# IO.net
KiCad netlist of a schematic drawn in Altium Designer
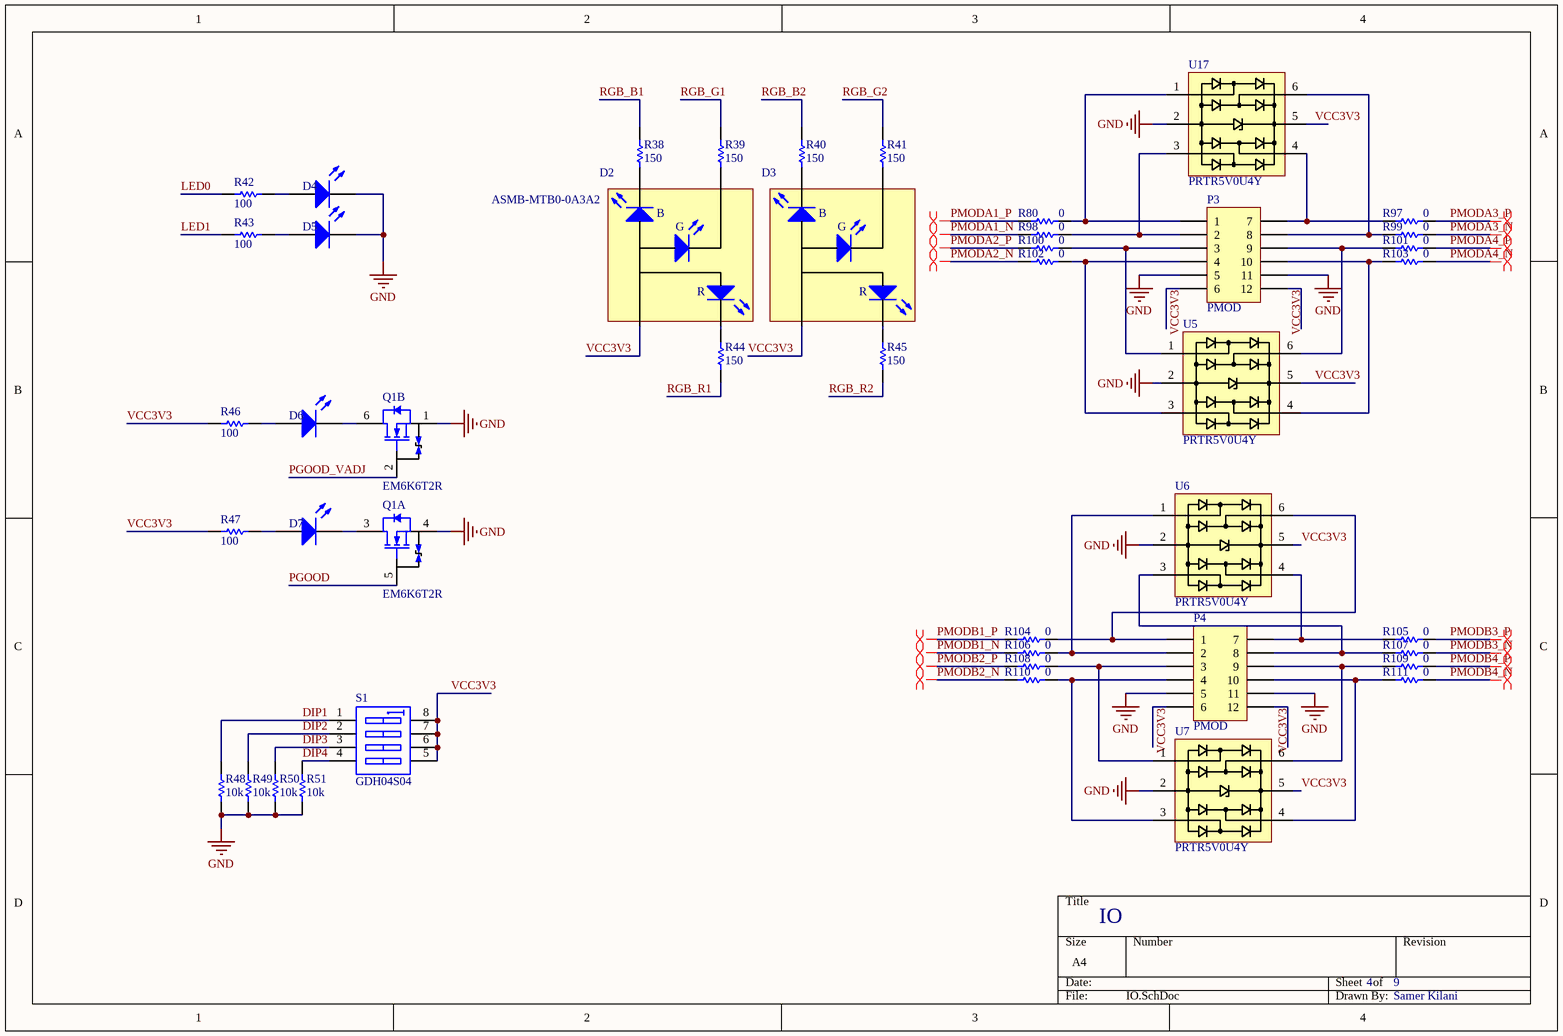
[diagram p0: IO.SchDoc]

(export (version "E")
  (design (tool "Eeschema 10.0.6"))
  (components
    (comp (ref "D2")
      (value "ASMB-MTB0-0A3A2")
      (footprint "ASMB-MTB0-0A3A2")
      (description "Typical INFRARED GaAs LED")
      (fields (field (name "PUBLISHER") "Altium Limited"))
      (libsource (lib "atfclib") (part "LED_RGB"))
    )
    (comp (ref "D3")
      (value "ASMB-MTB0-0A3A2")
      (footprint "ASMB-MTB0-0A3A2")
      (description "Typical INFRARED GaAs LED")
      (fields (field (name "PUBLISHER") "Altium Limited"))
      (libsource (lib "atfclib") (part "LED_RGB"))
    )
    (comp (ref "D4")
      (value "KPT-1608EC")
      (footprint "KP-1608QBC-D")
      (fields (field (name "PUBLISHER") "Altium Limited"))
      (libsource (lib "atfclib") (part "LED"))
    )
    (comp (ref "D5")
      (value "KPT-1608EC")
      (footprint "KP-1608QBC-D")
      (fields (field (name "PUBLISHER") "Altium Limited"))
      (libsource (lib "atfclib") (part "LED"))
    )
    (comp (ref "D6")
      (value "KPT-1608EC")
      (footprint "KP-1608QBC-D")
      (fields (field (name "PUBLISHER") "Altium Limited"))
      (libsource (lib "atfclib") (part "LED"))
    )
    (comp (ref "D7")
      (value "KPT-1608EC")
      (footprint "KP-1608QBC-D")
      (fields (field (name "PUBLISHER") "Altium Limited"))
      (libsource (lib "atfclib") (part "LED"))
    )
    (comp (ref "P3")
      (value "PMOD")
      (footprint "PMOD_12")
      (description "Header, 6-Pin, Dual row")
      (fields (field (name "PUBLISHER") "Altium Limited"))
      (libsource (lib "Miscellaneous Connectors") (part "Header 6X2A"))
    )
    (comp (ref "P4")
      (value "PMOD")
      (footprint "PMOD_12")
      (description "Header, 6-Pin, Dual row")
      (fields (field (name "PUBLISHER") "Altium Limited"))
      (libsource (lib "Miscellaneous Connectors") (part "Header 6X2A"))
    )
    (comp (ref "Q1") (value "EM6K6T2R") (footprint "SOT-563") (libsource (lib "atfclib") (part "EM6K6")))
    (comp (ref "R38")
      (value "150")
      (footprint "R0402")
      (description "Resistor")
      (fields (field (name "Comment") "Res"))
      (libsource (lib "atfclib") (part "Res"))
    )
    (comp (ref "R39")
      (value "150")
      (footprint "R0402")
      (description "Resistor")
      (fields (field (name "Comment") "Res"))
      (libsource (lib "atfclib") (part "Res"))
    )
    (comp (ref "R40")
      (value "150")
      (footprint "R0402")
      (description "Resistor")
      (fields (field (name "Comment") "Res"))
      (libsource (lib "atfclib") (part "Res"))
    )
    (comp (ref "R41")
      (value "150")
      (footprint "R0402")
      (description "Resistor")
      (fields (field (name "Comment") "Res"))
      (libsource (lib "atfclib") (part "Res"))
    )
    (comp (ref "R42")
      (value "100")
      (footprint "R0402")
      (description "Resistor")
      (fields (field (name "Comment") "Res"))
      (libsource (lib "atfclib") (part "Res"))
    )
    (comp (ref "R43")
      (value "100")
      (footprint "R0402")
      (description "Resistor")
      (fields (field (name "Comment") "Res"))
      (libsource (lib "atfclib") (part "Res"))
    )
    (comp (ref "R44")
      (value "150")
      (footprint "R0402")
      (description "Resistor")
      (fields (field (name "Comment") "Res"))
      (libsource (lib "atfclib") (part "Res"))
    )
    (comp (ref "R45")
      (value "150")
      (footprint "R0402")
      (description "Resistor")
      (fields (field (name "Comment") "Res"))
      (libsource (lib "atfclib") (part "Res"))
    )
    (comp (ref "R46")
      (value "100")
      (footprint "R0402")
      (description "Resistor")
      (fields (field (name "Comment") "Res"))
      (libsource (lib "atfclib") (part "Res"))
    )
    (comp (ref "R47")
      (value "100")
      (footprint "R0402")
      (description "Resistor")
      (fields (field (name "Comment") "Res"))
      (libsource (lib "atfclib") (part "Res"))
    )
    (comp (ref "R48")
      (value "10k")
      (footprint "R0402")
      (description "Resistor")
      (fields (field (name "Comment") "Res"))
      (libsource (lib "atfclib") (part "Res"))
    )
    (comp (ref "R49")
      (value "10k")
      (footprint "R0402")
      (description "Resistor")
      (fields (field (name "Comment") "Res"))
      (libsource (lib "atfclib") (part "Res"))
    )
    (comp (ref "R50")
      (value "10k")
      (footprint "R0402")
      (description "Resistor")
      (fields (field (name "Comment") "Res"))
      (libsource (lib "atfclib") (part "Res"))
    )
    (comp (ref "R51")
      (value "10k")
      (footprint "R0402")
      (description "Resistor")
      (fields (field (name "Comment") "Res"))
      (libsource (lib "atfclib") (part "Res"))
    )
    (comp (ref "R80")
      (value "0")
      (footprint "R0402")
      (description "Resistor")
      (fields (field (name "Comment") "Res"))
      (libsource (lib "atfclib") (part "Res"))
    )
    (comp (ref "R97")
      (value "0")
      (footprint "R0402")
      (description "Resistor")
      (fields (field (name "Comment") "Res"))
      (libsource (lib "atfclib") (part "Res"))
    )
    (comp (ref "R98")
      (value "0")
      (footprint "R0402")
      (description "Resistor")
      (fields (field (name "Comment") "Res"))
      (libsource (lib "atfclib") (part "Res"))
    )
    (comp (ref "R99")
      (value "0")
      (footprint "R0402")
      (description "Resistor")
      (fields (field (name "Comment") "Res"))
      (libsource (lib "atfclib") (part "Res"))
    )
    (comp (ref "R100")
      (value "0")
      (footprint "R0402")
      (description "Resistor")
      (fields (field (name "Comment") "Res"))
      (libsource (lib "atfclib") (part "Res"))
    )
    (comp (ref "R101")
      (value "0")
      (footprint "R0402")
      (description "Resistor")
      (fields (field (name "Comment") "Res"))
      (libsource (lib "atfclib") (part "Res"))
    )
    (comp (ref "R102")
      (value "0")
      (footprint "R0402")
      (description "Resistor")
      (fields (field (name "Comment") "Res"))
      (libsource (lib "atfclib") (part "Res"))
    )
    (comp (ref "R103")
      (value "0")
      (footprint "R0402")
      (description "Resistor")
      (fields (field (name "Comment") "Res"))
      (libsource (lib "atfclib") (part "Res"))
    )
    (comp (ref "R104")
      (value "0")
      (footprint "R0402")
      (description "Resistor")
      (fields (field (name "Comment") "Res"))
      (libsource (lib "atfclib") (part "Res"))
    )
    (comp (ref "R105")
      (value "0")
      (footprint "R0402")
      (description "Resistor")
      (fields (field (name "Comment") "Res"))
      (libsource (lib "atfclib") (part "Res"))
    )
    (comp (ref "R106")
      (value "0")
      (footprint "R0402")
      (description "Resistor")
      (fields (field (name "Comment") "Res"))
      (libsource (lib "atfclib") (part "Res"))
    )
    (comp (ref "R107")
      (value "0")
      (footprint "R0402")
      (description "Resistor")
      (fields (field (name "Comment") "Res"))
      (libsource (lib "atfclib") (part "Res"))
    )
    (comp (ref "R108")
      (value "0")
      (footprint "R0402")
      (description "Resistor")
      (fields (field (name "Comment") "Res"))
      (libsource (lib "atfclib") (part "Res"))
    )
    (comp (ref "R109")
      (value "0")
      (footprint "R0402")
      (description "Resistor")
      (fields (field (name "Comment") "Res"))
      (libsource (lib "atfclib") (part "Res"))
    )
    (comp (ref "R110")
      (value "0")
      (footprint "R0402")
      (description "Resistor")
      (fields (field (name "Comment") "Res"))
      (libsource (lib "atfclib") (part "Res"))
    )
    (comp (ref "R111")
      (value "0")
      (footprint "R0402")
      (description "Resistor")
      (fields (field (name "Comment") "Res"))
      (libsource (lib "atfclib") (part "Res"))
    )
    (comp (ref "S1")
      (value "GDH04S04")
      (footprint "DIP-SOP8")
      (description "DIP Switch, 4 Position, SPST")
      (fields (field (name "PUBLISHER") "Altium Limited"))
      (libsource (lib "Miscellaneous Devices") (part "SW DIP-4"))
    )
    (comp (ref "U5")
      (value "PRTR5V0U4Y")
      (footprint "SOT363")
      (libsource (lib "atfclib") (part "PRTR5V0U4Y"))
    )
    (comp (ref "U6")
      (value "PRTR5V0U4Y")
      (footprint "SOT363")
      (libsource (lib "atfclib") (part "PRTR5V0U4Y"))
    )
    (comp (ref "U7")
      (value "PRTR5V0U4Y")
      (footprint "SOT363")
      (libsource (lib "atfclib") (part "PRTR5V0U4Y"))
    )
    (comp (ref "U17")
      (value "PRTR5V0U4Y")
      (footprint "SOT363")
      (libsource (lib "atfclib") (part "PRTR5V0U4Y"))
    )
  )
  (nets
    (net (code "1") (name "/DIP1") (class "Default")
      (node (ref "R48") (pin "1") (pinfunction "1_1") (pintype "passive"))
      (node (ref "S1") (pin "1") (pinfunction "A1_1") (pintype "passive"))
    )
    (net (code "2") (name "/DIP2") (class "Default")
      (node (ref "R49") (pin "1") (pinfunction "1_1") (pintype "passive"))
      (node (ref "S1") (pin "2") (pinfunction "A2_2") (pintype "passive"))
    )
    (net (code "3") (name "/DIP3") (class "Default")
      (node (ref "R50") (pin "1") (pinfunction "1_1") (pintype "passive"))
      (node (ref "S1") (pin "3") (pinfunction "A3_3") (pintype "passive"))
    )
    (net (code "4") (name "/DIP4") (class "Default")
      (node (ref "R51") (pin "1") (pinfunction "1_1") (pintype "passive"))
      (node (ref "S1") (pin "4") (pinfunction "A4_4") (pintype "passive"))
    )
    (net (code "5") (name "/LED0") (class "Default")
      (node (ref "R42") (pin "2") (pinfunction "2_2") (pintype "passive"))
    )
    (net (code "6") (name "/LED1") (class "Default")
      (node (ref "R43") (pin "2") (pinfunction "2_2") (pintype "passive"))
    )
    (net (code "7") (name "/PGOOD") (class "Default")
      (node (ref "Q1") (pin "5") (pinfunction "G1_5") (pintype "passive"))
    )
    (net (code "8") (name "/PGOOD_VADJ") (class "Default")
      (node (ref "Q1") (pin "2") (pinfunction "G1_2") (pintype "passive"))
    )
    (net (code "9") (name "/PMODA1_N") (class "Default")
      (node (ref "R98") (pin "1") (pinfunction "1_1") (pintype "passive"))
    )
    (net (code "10") (name "/PMODA1_P") (class "Default")
      (node (ref "R80") (pin "1") (pinfunction "1_1") (pintype "passive"))
    )
    (net (code "11") (name "/PMODA2_N") (class "Default")
      (node (ref "R102") (pin "1") (pinfunction "1_1") (pintype "passive"))
    )
    (net (code "12") (name "/PMODA2_P") (class "Default")
      (node (ref "R100") (pin "1") (pinfunction "1_1") (pintype "passive"))
    )
    (net (code "13") (name "/PMODA3_N") (class "Default")
      (node (ref "R99") (pin "2") (pinfunction "2_2") (pintype "passive"))
    )
    (net (code "14") (name "/PMODA3_P") (class "Default")
      (node (ref "R97") (pin "2") (pinfunction "2_2") (pintype "passive"))
    )
    (net (code "15") (name "/PMODA4_N") (class "Default")
      (node (ref "R103") (pin "2") (pinfunction "2_2") (pintype "passive"))
    )
    (net (code "16") (name "/PMODA4_P") (class "Default")
      (node (ref "R101") (pin "2") (pinfunction "2_2") (pintype "passive"))
    )
    (net (code "17") (name "/PMODB1_N") (class "Default")
      (node (ref "R106") (pin "1") (pinfunction "1_1") (pintype "passive"))
    )
    (net (code "18") (name "/PMODB1_P") (class "Default")
      (node (ref "R104") (pin "1") (pinfunction "1_1") (pintype "passive"))
    )
    (net (code "19") (name "/PMODB2_N") (class "Default")
      (node (ref "R110") (pin "1") (pinfunction "1_1") (pintype "passive"))
    )
    (net (code "20") (name "/PMODB2_P") (class "Default")
      (node (ref "R108") (pin "1") (pinfunction "1_1") (pintype "passive"))
    )
    (net (code "21") (name "/PMODB3_N") (class "Default")
      (node (ref "R107") (pin "2") (pinfunction "2_2") (pintype "passive"))
    )
    (net (code "22") (name "/PMODB3_P") (class "Default")
      (node (ref "R105") (pin "2") (pinfunction "2_2") (pintype "passive"))
    )
    (net (code "23") (name "/PMODB4_N") (class "Default")
      (node (ref "R111") (pin "2") (pinfunction "2_2") (pintype "passive"))
    )
    (net (code "24") (name "/PMODB4_P") (class "Default")
      (node (ref "R109") (pin "2") (pinfunction "2_2") (pintype "passive"))
    )
    (net (code "25") (name "/RGB_B1") (class "Default")
      (node (ref "R38") (pin "2") (pinfunction "2_2") (pintype "passive"))
    )
    (net (code "26") (name "/RGB_B2") (class "Default")
      (node (ref "R40") (pin "2") (pinfunction "2_2") (pintype "passive"))
    )
    (net (code "27") (name "/RGB_G1") (class "Default")
      (node (ref "R39") (pin "2") (pinfunction "2_2") (pintype "passive"))
    )
    (net (code "28") (name "/RGB_G2") (class "Default")
      (node (ref "R41") (pin "2") (pinfunction "2_2") (pintype "passive"))
    )
    (net (code "29") (name "/RGB_R1") (class "Default")
      (node (ref "R44") (pin "1") (pinfunction "1_1") (pintype "passive"))
    )
    (net (code "30") (name "/RGB_R2") (class "Default")
      (node (ref "R45") (pin "1") (pinfunction "1_1") (pintype "passive"))
    )
    (net (code "31") (name "/VCC3V3") (class "Default")
      (node (ref "D2") (pin "1") (pinfunction "A_1") (pintype "passive"))
      (node (ref "D3") (pin "1") (pinfunction "A_1") (pintype "passive"))
      (node (ref "P3") (pin "12") (pinfunction "12_12") (pintype "passive"))
      (node (ref "P3") (pin "6") (pinfunction "6_6") (pintype "passive"))
      (node (ref "P4") (pin "12") (pinfunction "12_12") (pintype "passive"))
      (node (ref "P4") (pin "6") (pinfunction "6_6") (pintype "passive"))
      (node (ref "R46") (pin "2") (pinfunction "2_2") (pintype "passive"))
      (node (ref "R47") (pin "2") (pinfunction "2_2") (pintype "passive"))
      (node (ref "S1") (pin "5") (pinfunction "B4_5") (pintype "passive"))
      (node (ref "S1") (pin "6") (pinfunction "B3_6") (pintype "passive"))
      (node (ref "S1") (pin "7") (pinfunction "B2_7") (pintype "passive"))
      (node (ref "S1") (pin "8") (pinfunction "B1_8") (pintype "passive"))
      (node (ref "U17") (pin "5") (pinfunction "5_5") (pintype "passive"))
      (node (ref "U5") (pin "5") (pinfunction "5_5") (pintype "passive"))
      (node (ref "U6") (pin "5") (pinfunction "5_5") (pintype "passive"))
      (node (ref "U7") (pin "5") (pinfunction "5_5") (pintype "passive"))
    )
    (net (code "32") (name "GND") (class "Default")
      (node (ref "D4") (pin "2") (pinfunction "K_2") (pintype "passive"))
      (node (ref "D5") (pin "2") (pinfunction "K_2") (pintype "passive"))
      (node (ref "P3") (pin "11") (pinfunction "11_11") (pintype "passive"))
      (node (ref "P3") (pin "5") (pinfunction "5_5") (pintype "passive"))
      (node (ref "P4") (pin "11") (pinfunction "11_11") (pintype "passive"))
      (node (ref "P4") (pin "5") (pinfunction "5_5") (pintype "passive"))
      (node (ref "Q1") (pin "1") (pinfunction "S1_1") (pintype "passive"))
      (node (ref "Q1") (pin "4") (pinfunction "S1_4") (pintype "passive"))
      (node (ref "R48") (pin "2") (pinfunction "2_2") (pintype "passive"))
      (node (ref "R49") (pin "2") (pinfunction "2_2") (pintype "passive"))
      (node (ref "R50") (pin "2") (pinfunction "2_2") (pintype "passive"))
      (node (ref "R51") (pin "2") (pinfunction "2_2") (pintype "passive"))
      (node (ref "U17") (pin "2") (pinfunction "2_2") (pintype "passive"))
      (node (ref "U5") (pin "2") (pinfunction "2_2") (pintype "passive"))
      (node (ref "U6") (pin "2") (pinfunction "2_2") (pintype "passive"))
      (node (ref "U7") (pin "2") (pinfunction "2_2") (pintype "passive"))
    )
    (net (code "33") (name "Net-(D2-B)") (class "Default")
      (node (ref "D2") (pin "2") (pinfunction "B_2") (pintype "passive"))
      (node (ref "R38") (pin "1") (pinfunction "1_1") (pintype "passive"))
    )
    (net (code "34") (name "Net-(D2-G)") (class "Default")
      (node (ref "D2") (pin "3") (pinfunction "G_3") (pintype "passive"))
      (node (ref "R39") (pin "1") (pinfunction "1_1") (pintype "passive"))
    )
    (net (code "35") (name "Net-(D2-R)") (class "Default")
      (node (ref "D2") (pin "4") (pinfunction "R_4") (pintype "passive"))
      (node (ref "R44") (pin "2") (pinfunction "2_2") (pintype "passive"))
    )
    (net (code "36") (name "Net-(D3-B)") (class "Default")
      (node (ref "D3") (pin "2") (pinfunction "B_2") (pintype "passive"))
      (node (ref "R40") (pin "1") (pinfunction "1_1") (pintype "passive"))
    )
    (net (code "37") (name "Net-(D3-G)") (class "Default")
      (node (ref "D3") (pin "3") (pinfunction "G_3") (pintype "passive"))
      (node (ref "R41") (pin "1") (pinfunction "1_1") (pintype "passive"))
    )
    (net (code "38") (name "Net-(D3-R)") (class "Default")
      (node (ref "D3") (pin "4") (pinfunction "R_4") (pintype "passive"))
      (node (ref "R45") (pin "2") (pinfunction "2_2") (pintype "passive"))
    )
    (net (code "39") (name "Net-(D4-A)") (class "Default")
      (node (ref "D4") (pin "1") (pinfunction "A_1") (pintype "passive"))
      (node (ref "R42") (pin "1") (pinfunction "1_1") (pintype "passive"))
    )
    (net (code "40") (name "Net-(D5-A)") (class "Default")
      (node (ref "D5") (pin "1") (pinfunction "A_1") (pintype "passive"))
      (node (ref "R43") (pin "1") (pinfunction "1_1") (pintype "passive"))
    )
    (net (code "41") (name "Net-(D6-A)") (class "Default")
      (node (ref "D6") (pin "1") (pinfunction "A_1") (pintype "passive"))
      (node (ref "R46") (pin "1") (pinfunction "1_1") (pintype "passive"))
    )
    (net (code "42") (name "Net-(D6-K)") (class "Default")
      (node (ref "D6") (pin "2") (pinfunction "K_2") (pintype "passive"))
      (node (ref "Q1") (pin "6") (pinfunction "D1_6") (pintype "passive"))
    )
    (net (code "43") (name "Net-(D7-A)") (class "Default")
      (node (ref "D7") (pin "1") (pinfunction "A_1") (pintype "passive"))
      (node (ref "R47") (pin "1") (pinfunction "1_1") (pintype "passive"))
    )
    (net (code "44") (name "Net-(D7-K)") (class "Default")
      (node (ref "D7") (pin "2") (pinfunction "K_2") (pintype "passive"))
      (node (ref "Q1") (pin "3") (pinfunction "D1_3") (pintype "passive"))
    )
    (net (code "45") (name "Net-(P3-Pad1)") (class "Default")
      (node (ref "P3") (pin "1") (pinfunction "1_1") (pintype "passive"))
      (node (ref "R80") (pin "2") (pinfunction "2_2") (pintype "passive"))
      (node (ref "U17") (pin "1") (pinfunction "1_1") (pintype "passive"))
    )
    (net (code "46") (name "Net-(P3-Pad2)") (class "Default")
      (node (ref "P3") (pin "2") (pinfunction "2_2") (pintype "passive"))
      (node (ref "R98") (pin "2") (pinfunction "2_2") (pintype "passive"))
      (node (ref "U17") (pin "3") (pinfunction "3_3") (pintype "passive"))
    )
    (net (code "47") (name "Net-(P3-Pad3)") (class "Default")
      (node (ref "P3") (pin "3") (pinfunction "3_3") (pintype "passive"))
      (node (ref "R100") (pin "2") (pinfunction "2_2") (pintype "passive"))
      (node (ref "U5") (pin "1") (pinfunction "1_1") (pintype "passive"))
    )
    (net (code "48") (name "Net-(P3-Pad4)") (class "Default")
      (node (ref "P3") (pin "4") (pinfunction "4_4") (pintype "passive"))
      (node (ref "R102") (pin "2") (pinfunction "2_2") (pintype "passive"))
      (node (ref "U5") (pin "3") (pinfunction "3_3") (pintype "passive"))
    )
    (net (code "49") (name "Net-(P3-Pad7)") (class "Default")
      (node (ref "P3") (pin "7") (pinfunction "7_7") (pintype "passive"))
      (node (ref "R97") (pin "1") (pinfunction "1_1") (pintype "passive"))
      (node (ref "U17") (pin "4") (pinfunction "4_4") (pintype "passive"))
    )
    (net (code "50") (name "Net-(P3-Pad8)") (class "Default")
      (node (ref "P3") (pin "8") (pinfunction "8_8") (pintype "passive"))
      (node (ref "R99") (pin "1") (pinfunction "1_1") (pintype "passive"))
      (node (ref "U17") (pin "6") (pinfunction "6_6") (pintype "passive"))
    )
    (net (code "51") (name "Net-(P3-Pad9)") (class "Default")
      (node (ref "P3") (pin "9") (pinfunction "9_9") (pintype "passive"))
      (node (ref "R101") (pin "1") (pinfunction "1_1") (pintype "passive"))
      (node (ref "U5") (pin "6") (pinfunction "6_6") (pintype "passive"))
    )
    (net (code "52") (name "Net-(P3-Pad10)") (class "Default")
      (node (ref "P3") (pin "10") (pinfunction "10_10") (pintype "passive"))
      (node (ref "R103") (pin "1") (pinfunction "1_1") (pintype "passive"))
      (node (ref "U5") (pin "4") (pinfunction "4_4") (pintype "passive"))
    )
    (net (code "53") (name "Net-(P4-Pad1)") (class "Default")
      (node (ref "P4") (pin "1") (pinfunction "1_1") (pintype "passive"))
      (node (ref "R104") (pin "2") (pinfunction "2_2") (pintype "passive"))
      (node (ref "U6") (pin "6") (pinfunction "6_6") (pintype "passive"))
    )
    (net (code "54") (name "Net-(P4-Pad2)") (class "Default")
      (node (ref "P4") (pin "2") (pinfunction "2_2") (pintype "passive"))
      (node (ref "R106") (pin "2") (pinfunction "2_2") (pintype "passive"))
      (node (ref "U6") (pin "1") (pinfunction "1_1") (pintype "passive"))
    )
    (net (code "55") (name "Net-(P4-Pad3)") (class "Default")
      (node (ref "P4") (pin "3") (pinfunction "3_3") (pintype "passive"))
      (node (ref "R108") (pin "2") (pinfunction "2_2") (pintype "passive"))
      (node (ref "U7") (pin "1") (pinfunction "1_1") (pintype "passive"))
    )
    (net (code "56") (name "Net-(P4-Pad4)") (class "Default")
      (node (ref "P4") (pin "4") (pinfunction "4_4") (pintype "passive"))
      (node (ref "R110") (pin "2") (pinfunction "2_2") (pintype "passive"))
      (node (ref "U7") (pin "3") (pinfunction "3_3") (pintype "passive"))
    )
    (net (code "57") (name "Net-(P4-Pad7)") (class "Default")
      (node (ref "P4") (pin "7") (pinfunction "7_7") (pintype "passive"))
      (node (ref "R105") (pin "1") (pinfunction "1_1") (pintype "passive"))
      (node (ref "U6") (pin "4") (pinfunction "4_4") (pintype "passive"))
    )
    (net (code "58") (name "Net-(P4-Pad8)") (class "Default")
      (node (ref "P4") (pin "8") (pinfunction "8_8") (pintype "passive"))
      (node (ref "R107") (pin "1") (pinfunction "1_1") (pintype "passive"))
      (node (ref "U6") (pin "3") (pinfunction "3_3") (pintype "passive"))
    )
    (net (code "59") (name "Net-(P4-Pad9)") (class "Default")
      (node (ref "P4") (pin "9") (pinfunction "9_9") (pintype "passive"))
      (node (ref "R109") (pin "1") (pinfunction "1_1") (pintype "passive"))
      (node (ref "U7") (pin "6") (pinfunction "6_6") (pintype "passive"))
    )
    (net (code "60") (name "Net-(P4-Pad10)") (class "Default")
      (node (ref "P4") (pin "10") (pinfunction "10_10") (pintype "passive"))
      (node (ref "R111") (pin "1") (pinfunction "1_1") (pintype "passive"))
      (node (ref "U7") (pin "4") (pinfunction "4_4") (pintype "passive"))
    )
  )
)
